# Genesis_giraffe1.net
KiCad netlist of a schematic drawn in EAGLE
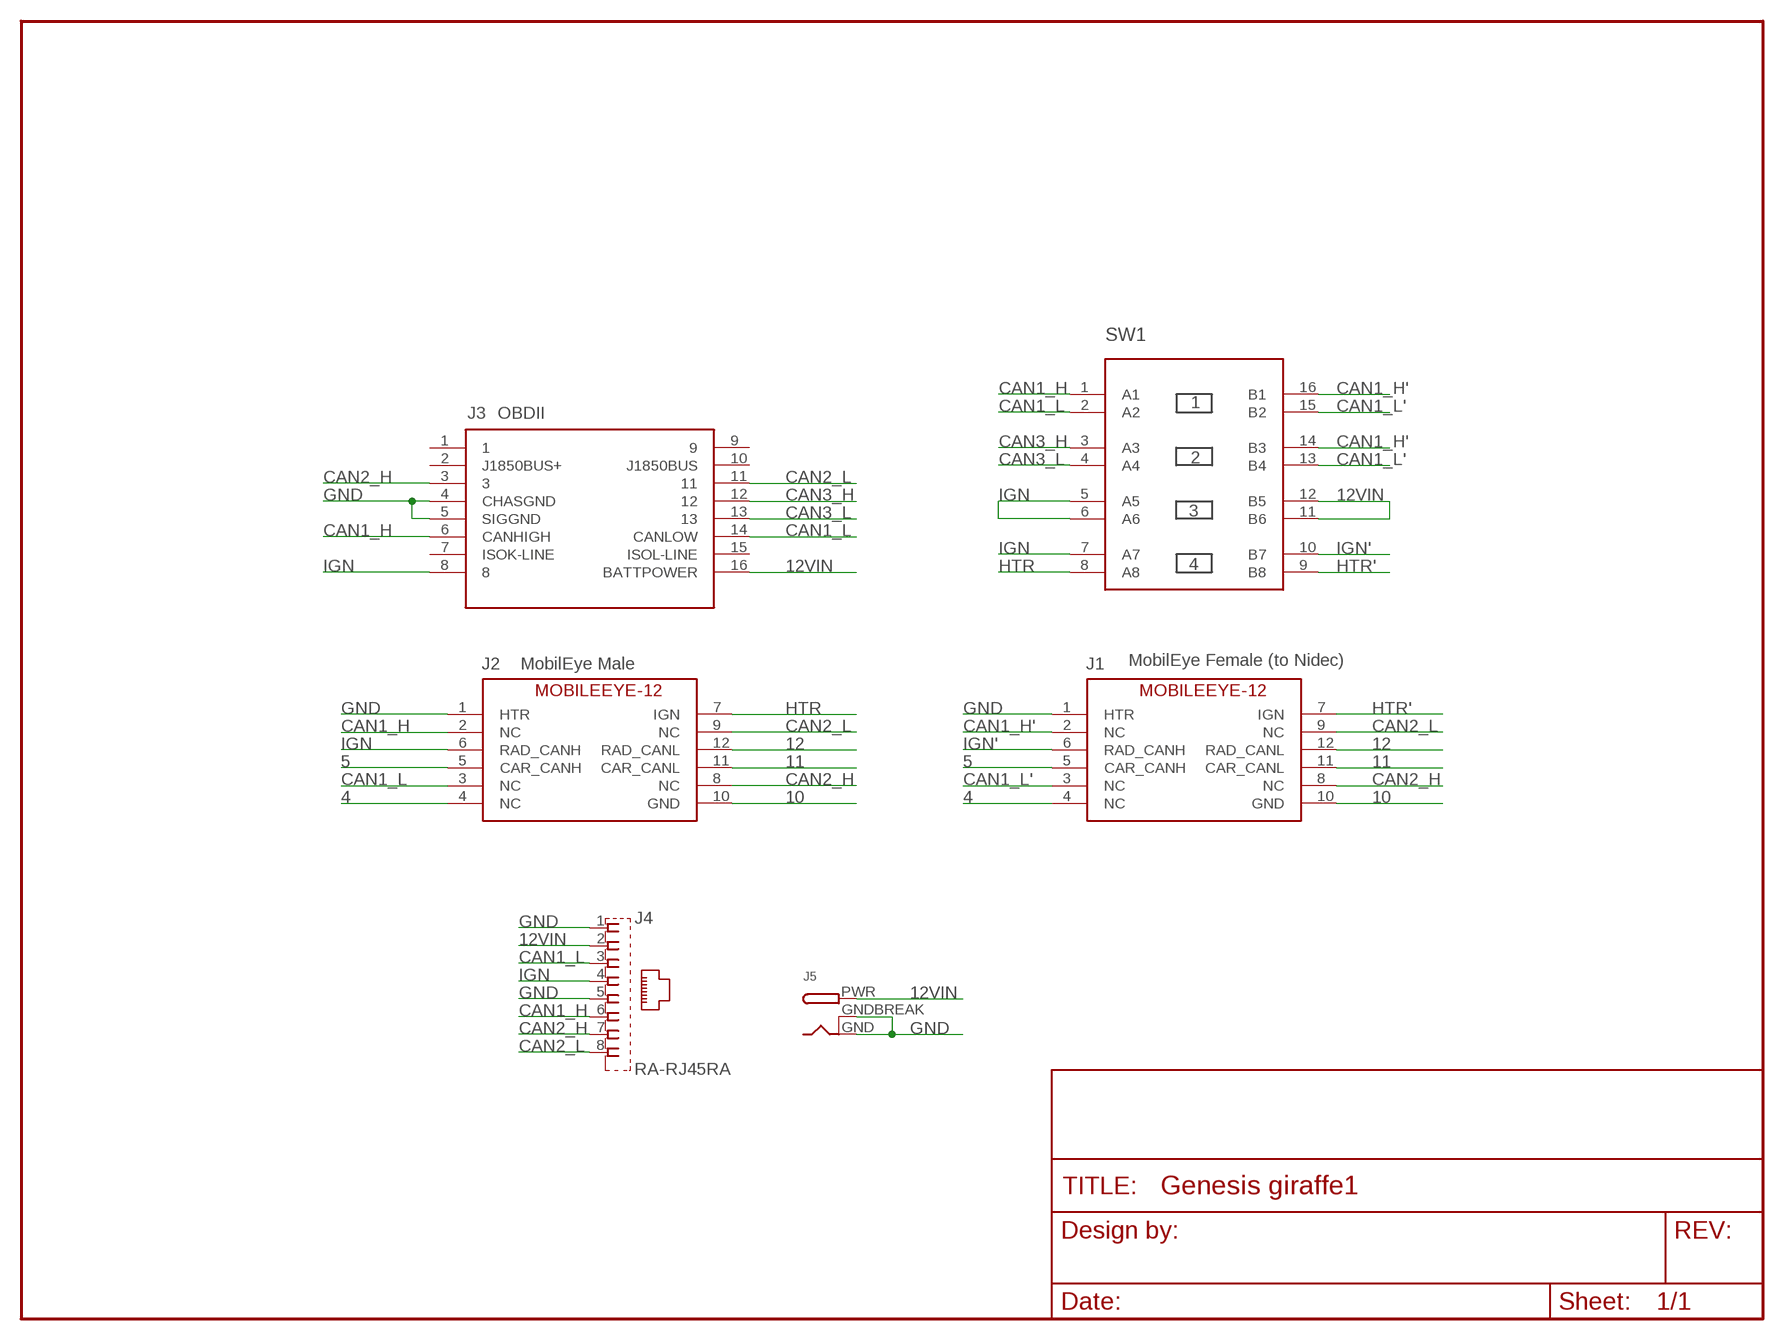
[diagram p0: schematic, sheet 1]

(export (version "E")
  (design (tool "Eeschema 10.0.6"))
  (components
    (comp (ref "FRAME1")
      (value "FRAME-LETTERNO_PACKAGE")
      (footprint "eagle-import:DUMMY")
      (fields (field (name "DESIGNER") "Nobody"))
      (libsource (lib "eagle-import") (part "FRAME-LETTERNO_PACKAGE"))
    )
    (comp (ref "J1")
      (value "MOBILEEYE-12FEMALE")
      (footprint "eagle-import:2X6-TE-FEMALE")
      (libsource (lib "eagle-import") (part "MOBILEEYE-12FEMALE"))
    )
    (comp (ref "J2")
      (value "MOBILEEYE-12MALE")
      (footprint "eagle-import:2X6-TE-RA")
      (libsource (lib "eagle-import") (part "MOBILEEYE-12MALE"))
    )
    (comp (ref "J3")
      (value "OBDII-FEMALE-CUT")
      (footprint "eagle-import:OBDII-FEMALE-MIDCUT")
      (libsource (lib "eagle-import") (part "OBDII-FEMALE-CUT"))
    )
    (comp (ref "J4")
      (value "RA-RJ45RA")
      (footprint "eagle-import:RA-RJ45")
      (libsource (lib "eagle-import") (part "RA-RJ45RA"))
    )
    (comp (ref "J5")
      (value "DCBARRELPTH")
      (footprint "eagle-import:DCJACK_2MM_PTH")
      (libsource (lib "eagle-import") (part "DCBARRELPTH"))
    )
    (comp (ref "SW1")
      (value "4XDPSTSMT")
      (footprint "eagle-import:4-DPST")
      (libsource (lib "eagle-import") (part "4XDPSTSMT"))
    )
  )
  (nets
    (net (code "1") (name "/4") (class "Default")
      (node (ref "J1") (pin "4") (pinfunction "NC_4") (pintype "bidirectional"))
      (node (ref "J2") (pin "4") (pinfunction "NC_4") (pintype "bidirectional"))
    )
    (net (code "2") (name "/5") (class "Default")
      (node (ref "J1") (pin "5") (pinfunction "CAR_CANH_5") (pintype "bidirectional"))
      (node (ref "J2") (pin "5") (pinfunction "CAR_CANH_5") (pintype "bidirectional"))
    )
    (net (code "3") (name "/10") (class "Default")
      (node (ref "J1") (pin "10") (pinfunction "GND_10") (pintype "bidirectional"))
      (node (ref "J2") (pin "10") (pinfunction "GND_10") (pintype "bidirectional"))
    )
    (net (code "4") (name "/11") (class "Default")
      (node (ref "J1") (pin "11") (pinfunction "CAR_CANL_11") (pintype "bidirectional"))
      (node (ref "J2") (pin "11") (pinfunction "CAR_CANL_11") (pintype "bidirectional"))
    )
    (net (code "5") (name "/12") (class "Default")
      (node (ref "J1") (pin "12") (pinfunction "RAD_CANL_12") (pintype "bidirectional"))
      (node (ref "J2") (pin "12") (pinfunction "RAD_CANL_12") (pintype "bidirectional"))
    )
    (net (code "6") (name "/12VIN") (class "Default")
      (node (ref "J3") (pin "16") (pinfunction "BATTPOWER_16") (pintype "bidirectional"))
      (node (ref "J4") (pin "2") (pinfunction "2_2") (pintype "passive"))
      (node (ref "J5") (pin "PWR") (pinfunction "PWR_PWR") (pintype "power_in"))
      (node (ref "SW1") (pin "11") (pinfunction "B6_11") (pintype "bidirectional"))
      (node (ref "SW1") (pin "12") (pinfunction "B5_12") (pintype "bidirectional"))
    )
    (net (code "7") (name "/CAN1_H") (class "Default")
      (node (ref "J2") (pin "2") (pinfunction "NC_2") (pintype "bidirectional"))
      (node (ref "J3") (pin "6") (pinfunction "CANHIGH_6") (pintype "bidirectional"))
      (node (ref "J4") (pin "6") (pinfunction "6_6") (pintype "passive"))
      (node (ref "SW1") (pin "1") (pinfunction "A1_1") (pintype "bidirectional"))
    )
    (net (code "8") (name "/CAN1_H'") (class "Default")
      (node (ref "J1") (pin "2") (pinfunction "NC_2") (pintype "bidirectional"))
      (node (ref "SW1") (pin "14") (pinfunction "B3_14") (pintype "bidirectional"))
      (node (ref "SW1") (pin "16") (pinfunction "B1_16") (pintype "bidirectional"))
    )
    (net (code "9") (name "/CAN1_L") (class "Default")
      (node (ref "J2") (pin "3") (pinfunction "NC_3") (pintype "bidirectional"))
      (node (ref "J3") (pin "14") (pinfunction "CANLOW_14") (pintype "bidirectional"))
      (node (ref "J4") (pin "3") (pinfunction "3_3") (pintype "passive"))
      (node (ref "SW1") (pin "2") (pinfunction "A2_2") (pintype "bidirectional"))
    )
    (net (code "10") (name "/CAN1_L'") (class "Default")
      (node (ref "J1") (pin "3") (pinfunction "NC_3") (pintype "bidirectional"))
      (node (ref "SW1") (pin "13") (pinfunction "B4_13") (pintype "bidirectional"))
      (node (ref "SW1") (pin "15") (pinfunction "B2_15") (pintype "bidirectional"))
    )
    (net (code "11") (name "/CAN2_H") (class "Default")
      (node (ref "J1") (pin "8") (pinfunction "NC_8") (pintype "bidirectional"))
      (node (ref "J2") (pin "8") (pinfunction "NC_8") (pintype "bidirectional"))
      (node (ref "J3") (pin "3") (pinfunction "3_3") (pintype "bidirectional"))
      (node (ref "J4") (pin "7") (pinfunction "7_7") (pintype "passive"))
    )
    (net (code "12") (name "/CAN2_L") (class "Default")
      (node (ref "J1") (pin "9") (pinfunction "NC_9") (pintype "bidirectional"))
      (node (ref "J2") (pin "9") (pinfunction "NC_9") (pintype "bidirectional"))
      (node (ref "J3") (pin "11") (pinfunction "11_11") (pintype "bidirectional"))
      (node (ref "J4") (pin "8") (pinfunction "8_8") (pintype "passive"))
    )
    (net (code "13") (name "/CAN3_H") (class "Default")
      (node (ref "J3") (pin "12") (pinfunction "12_12") (pintype "bidirectional"))
      (node (ref "SW1") (pin "3") (pinfunction "A3_3") (pintype "bidirectional"))
    )
    (net (code "14") (name "/CAN3_L") (class "Default")
      (node (ref "J3") (pin "13") (pinfunction "13_13") (pintype "bidirectional"))
      (node (ref "SW1") (pin "4") (pinfunction "A4_4") (pintype "bidirectional"))
    )
    (net (code "15") (name "/GND") (class "Default")
      (node (ref "J1") (pin "1") (pinfunction "HTR_1") (pintype "bidirectional"))
      (node (ref "J2") (pin "1") (pinfunction "HTR_1") (pintype "bidirectional"))
      (node (ref "J3") (pin "4") (pinfunction "CHASGND_4") (pintype "bidirectional"))
      (node (ref "J3") (pin "5") (pinfunction "SIGGND_5") (pintype "bidirectional"))
      (node (ref "J4") (pin "1") (pinfunction "1_1") (pintype "passive"))
      (node (ref "J4") (pin "5") (pinfunction "5_5") (pintype "passive"))
      (node (ref "J5") (pin "GND") (pinfunction "GND_GND") (pintype "power_in"))
      (node (ref "J5") (pin "GNDBREAK") (pinfunction "GNDBREAK_GNDBREAK") (pintype "power_in"))
    )
    (net (code "16") (name "/HTR") (class "Default")
      (node (ref "J2") (pin "7") (pinfunction "IGN_7") (pintype "bidirectional"))
      (node (ref "SW1") (pin "8") (pinfunction "A8_8") (pintype "bidirectional"))
    )
    (net (code "17") (name "/HTR'") (class "Default")
      (node (ref "J1") (pin "7") (pinfunction "IGN_7") (pintype "bidirectional"))
      (node (ref "SW1") (pin "9") (pinfunction "B8_9") (pintype "bidirectional"))
    )
    (net (code "18") (name "/IGN") (class "Default")
      (node (ref "J2") (pin "6") (pinfunction "RAD_CANH_6") (pintype "bidirectional"))
      (node (ref "J3") (pin "8") (pinfunction "8_8") (pintype "bidirectional"))
      (node (ref "J4") (pin "4") (pinfunction "4_4") (pintype "passive"))
      (node (ref "SW1") (pin "5") (pinfunction "A5_5") (pintype "bidirectional"))
      (node (ref "SW1") (pin "6") (pinfunction "A6_6") (pintype "bidirectional"))
      (node (ref "SW1") (pin "7") (pinfunction "A7_7") (pintype "bidirectional"))
    )
    (net (code "19") (name "/IGN'") (class "Default")
      (node (ref "J1") (pin "6") (pinfunction "RAD_CANH_6") (pintype "bidirectional"))
      (node (ref "SW1") (pin "10") (pinfunction "B7_10") (pintype "bidirectional"))
    )
    (net (code "20") (name "unconnected-(J3-ISOK-LINE-Pad7)") (class "Default")
      (node (ref "J3") (pin "7") (pinfunction "ISOK-LINE_7") (pintype "bidirectional"))
    )
    (net (code "21") (name "unconnected-(J3-ISOL-LINE-Pad15)") (class "Default")
      (node (ref "J3") (pin "15") (pinfunction "ISOL-LINE_15") (pintype "bidirectional"))
    )
    (net (code "22") (name "unconnected-(J3-J1850BUS+-Pad2)") (class "Default")
      (node (ref "J3") (pin "2") (pinfunction "J1850BUS+_2") (pintype "bidirectional"))
    )
    (net (code "23") (name "unconnected-(J3-J1850BUS-Pad10)") (class "Default")
      (node (ref "J3") (pin "10") (pinfunction "J1850BUS_10") (pintype "bidirectional"))
    )
    (net (code "24") (name "unconnected-(J3-Pad1)") (class "Default")
      (node (ref "J3") (pin "1") (pinfunction "1_1") (pintype "bidirectional"))
    )
    (net (code "25") (name "unconnected-(J3-Pad9)") (class "Default")
      (node (ref "J3") (pin "9") (pinfunction "9_9") (pintype "bidirectional"))
    )
  )
)
